# Connectors.net
KiCad netlist of a schematic drawn in Altium Designer
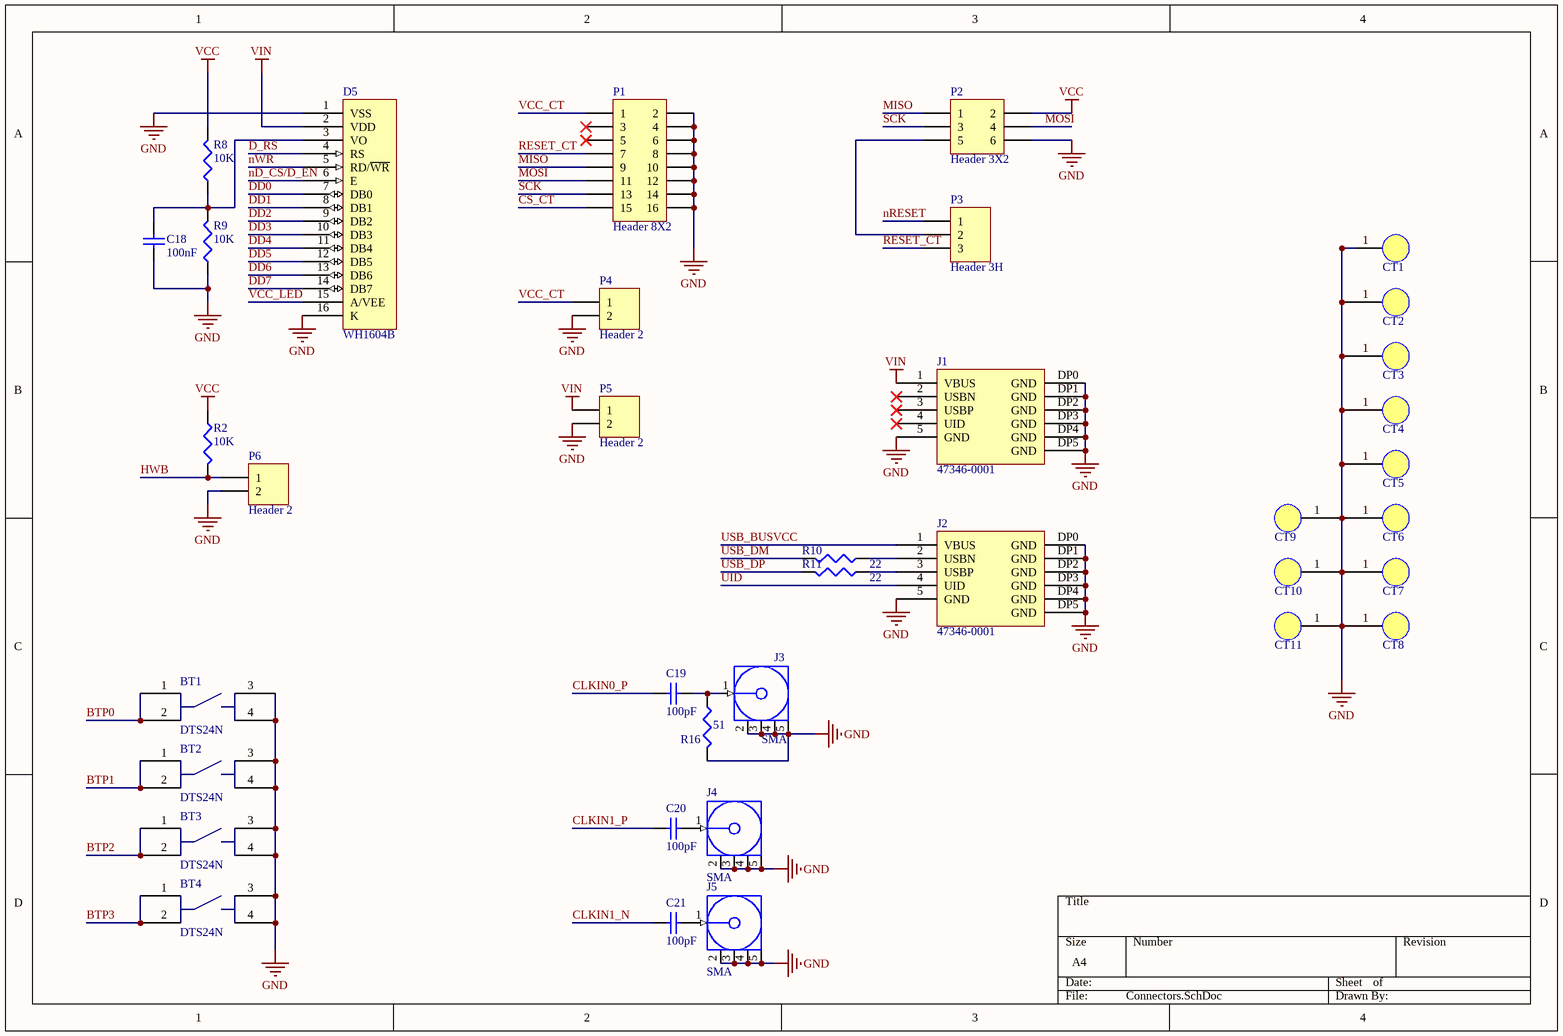
[diagram p0: Connectors.SchDoc]

(export (version "E")
  (design (tool "Eeschema 10.0.6"))
  (components
    (comp (ref "BT1") (value "DTS24N") (footprint "DTS24N") (libsource (lib "CTMBLib") (part "DTS24N")))
    (comp (ref "BT2") (value "DTS24N") (footprint "DTS24N") (libsource (lib "CTMBLib") (part "DTS24N")))
    (comp (ref "BT3") (value "DTS24N") (footprint "DTS24N") (libsource (lib "CTMBLib") (part "DTS24N")))
    (comp (ref "BT4") (value "DTS24N") (footprint "DTS24N") (libsource (lib "CTMBLib") (part "DTS24N")))
    (comp (ref "C18")
      (value "100nF")
      (footprint "1608[0603]")
      (description "Capacitor (Semiconductor SIM Model)")
      (fields (field (name "PUBLISHER") "Altium Limited"))
      (libsource (lib "Miscellaneous Devices") (part "Cap Semi"))
    )
    (comp (ref "C19")
      (value "100pF")
      (footprint "1608[0603]")
      (description "Capacitor (Semiconductor SIM Model)")
      (fields (field (name "PUBLISHER") "Altium Limited"))
      (libsource (lib "Miscellaneous Devices") (part "Cap Semi"))
    )
    (comp (ref "C20")
      (value "100pF")
      (footprint "1608[0603]")
      (description "Capacitor (Semiconductor SIM Model)")
      (fields (field (name "PUBLISHER") "Altium Limited"))
      (libsource (lib "Miscellaneous Devices") (part "Cap Semi"))
    )
    (comp (ref "C21")
      (value "100pF")
      (footprint "1608[0603]")
      (description "Capacitor (Semiconductor SIM Model)")
      (fields (field (name "PUBLISHER") "Altium Limited"))
      (libsource (lib "Miscellaneous Devices") (part "Cap Semi"))
    )
    (comp (ref "CT1")
      (value "MTHOLE_3mm")
      (footprint "MTHOLE")
      (libsource (lib "CTMBLib") (part "MTHOLE_3mm"))
    )
    (comp (ref "CT2")
      (value "MTHOLE_3mm")
      (footprint "MTHOLE")
      (libsource (lib "CTMBLib") (part "MTHOLE_3mm"))
    )
    (comp (ref "CT3")
      (value "MTHOLE_3mm")
      (footprint "MTHOLE")
      (libsource (lib "CTMBLib") (part "MTHOLE_3mm"))
    )
    (comp (ref "CT4")
      (value "MTHOLE_3mm")
      (footprint "MTHOLE")
      (libsource (lib "CTMBLib") (part "MTHOLE_3mm"))
    )
    (comp (ref "CT5")
      (value "MTHOLE_3mm")
      (footprint "MTHOLE")
      (libsource (lib "CTMBLib") (part "MTHOLE_3mm"))
    )
    (comp (ref "CT6")
      (value "MTHOLE_3mm")
      (footprint "MTHOLE")
      (libsource (lib "CTMBLib") (part "MTHOLE_3mm"))
    )
    (comp (ref "CT7")
      (value "MTHOLE_3mm")
      (footprint "MTHOLE")
      (libsource (lib "CTMBLib") (part "MTHOLE_3mm"))
    )
    (comp (ref "CT8")
      (value "MTHOLE_3mm")
      (footprint "MTHOLE")
      (libsource (lib "CTMBLib") (part "MTHOLE_3mm"))
    )
    (comp (ref "CT9")
      (value "MTHOLE_3mm")
      (footprint "MTHOLE")
      (libsource (lib "CTMBLib") (part "MTHOLE_3mm"))
    )
    (comp (ref "CT10")
      (value "MTHOLE_3mm")
      (footprint "MTHOLE")
      (libsource (lib "CTMBLib") (part "MTHOLE_3mm"))
    )
    (comp (ref "CT11")
      (value "MTHOLE_3mm")
      (footprint "MTHOLE")
      (libsource (lib "CTMBLib") (part "MTHOLE_3mm"))
    )
    (comp (ref "D5") (value "WH1604B") (footprint "WH1604A") (libsource (lib "CTMBLib") (part "WH1604B")))
    (comp (ref "J1")
      (value "47346-0001")
      (footprint "USB_MICRO")
      (description "Micro USB Molex")
      (libsource (lib "CTMBLib") (part "47346-0001"))
    )
    (comp (ref "J2")
      (value "47346-0001")
      (footprint "USB_MICRO")
      (description "Micro USB Molex")
      (libsource (lib "CTMBLib") (part "47346-0001"))
    )
    (comp (ref "J3") (value "SMA") (footprint "SMA") (libsource (lib "Integrated_Library1") (part "SMA")))
    (comp (ref "J4") (value "SMA") (footprint "SMA") (libsource (lib "Integrated_Library1") (part "SMA")))
    (comp (ref "J5") (value "SMA") (footprint "SMA") (libsource (lib "Integrated_Library1") (part "SMA")))
    (comp (ref "P1")
      (value "Header 8X2")
      (footprint "HDR2X8")
      (description "Header, 8-Pin, Dual row")
      (fields (field (name "PUBLISHER") "Altium Limited"))
      (libsource (lib "Miscellaneous Connectors") (part "Header 8X2"))
    )
    (comp (ref "P2")
      (value "Header 3X2")
      (footprint "HDR2X3")
      (description "Header, 3-Pin, Dual row")
      (fields (field (name "PUBLISHER") "Altium Limited"))
      (libsource (lib "Miscellaneous Connectors") (part "Header 3X2"))
    )
    (comp (ref "P3")
      (value "Header 3H")
      (footprint "HDR1X3H")
      (description "Header, 3-Pin, Right Angle")
      (fields (field (name "PUBLISHER") "Altium Limited"))
      (libsource (lib "Miscellaneous Connectors") (part "Header 3H"))
    )
    (comp (ref "P4")
      (value "Header 2")
      (footprint "HDR1X2")
      (description "Header, 2-Pin")
      (fields (field (name "PUBLISHER") "Altium Limited"))
      (libsource (lib "Miscellaneous Connectors") (part "Header 2"))
    )
    (comp (ref "P5")
      (value "Header 2")
      (footprint "HDR1X2")
      (description "Header, 2-Pin")
      (fields (field (name "PUBLISHER") "Altium Limited"))
      (libsource (lib "Miscellaneous Connectors") (part "Header 2"))
    )
    (comp (ref "P6")
      (value "Header 2")
      (footprint "HDR1X2")
      (description "Header, 2-Pin")
      (fields (field (name "PUBLISHER") "Altium Limited"))
      (libsource (lib "Miscellaneous Connectors") (part "Header 2"))
    )
    (comp (ref "R2")
      (value "10K")
      (footprint "J1-0603")
      (description "Resistor")
      (fields (field (name "PUBLISHER") "Altium Limited"))
      (libsource (lib "Miscellaneous Devices") (part "Res3"))
    )
    (comp (ref "R8")
      (value "10K")
      (footprint "J1-0603")
      (description "Resistor")
      (fields (field (name "PUBLISHER") "Altium Limited"))
      (libsource (lib "Miscellaneous Devices") (part "Res3"))
    )
    (comp (ref "R9")
      (value "10K")
      (footprint "J1-0603")
      (description "Resistor")
      (fields (field (name "PUBLISHER") "Altium Limited"))
      (libsource (lib "Miscellaneous Devices") (part "Res3"))
    )
    (comp (ref "R10")
      (value "22")
      (footprint "J1-0603")
      (description "Resistor")
      (fields (field (name "PUBLISHER") "Altium Limited"))
      (libsource (lib "Miscellaneous Devices") (part "Res3"))
    )
    (comp (ref "R11")
      (value "22")
      (footprint "J1-0603")
      (description "Resistor")
      (fields (field (name "PUBLISHER") "Altium Limited"))
      (libsource (lib "Miscellaneous Devices") (part "Res3"))
    )
    (comp (ref "R16")
      (value "51")
      (footprint "J1-0603")
      (description "Resistor")
      (fields (field (name "PUBLISHER") "Altium Limited"))
      (libsource (lib "Miscellaneous Devices") (part "Res3"))
    )
  )
  (nets
    (net (code "1") (name "/BTP0") (class "Default")
      (node (ref "BT1") (pin "1") (pinfunction "1_1") (pintype "passive"))
      (node (ref "BT1") (pin "2") (pinfunction "2_2") (pintype "passive"))
    )
    (net (code "2") (name "/BTP1") (class "Default")
      (node (ref "BT2") (pin "1") (pinfunction "1_1") (pintype "passive"))
      (node (ref "BT2") (pin "2") (pinfunction "2_2") (pintype "passive"))
    )
    (net (code "3") (name "/BTP2") (class "Default")
      (node (ref "BT3") (pin "1") (pinfunction "1_1") (pintype "passive"))
      (node (ref "BT3") (pin "2") (pinfunction "2_2") (pintype "passive"))
    )
    (net (code "4") (name "/BTP3") (class "Default")
      (node (ref "BT4") (pin "1") (pinfunction "1_1") (pintype "passive"))
      (node (ref "BT4") (pin "2") (pinfunction "2_2") (pintype "passive"))
    )
    (net (code "5") (name "/CLKIN0_P") (class "Default")
      (node (ref "C19") (pin "2") (pinfunction "2_2") (pintype "passive"))
    )
    (net (code "6") (name "/CLKIN1_N") (class "Default")
      (node (ref "C21") (pin "2") (pinfunction "2_2") (pintype "passive"))
    )
    (net (code "7") (name "/CLKIN1_P") (class "Default")
      (node (ref "C20") (pin "2") (pinfunction "2_2") (pintype "passive"))
    )
    (net (code "8") (name "/CS_CT") (class "Default")
      (node (ref "P1") (pin "15") (pinfunction "15_15") (pintype "passive"))
    )
    (net (code "9") (name "/DD0") (class "Default")
      (node (ref "D5") (pin "7") (pinfunction "DB0_7") (pintype "bidirectional"))
    )
    (net (code "10") (name "/DD1") (class "Default")
      (node (ref "D5") (pin "8") (pinfunction "DB1_8") (pintype "bidirectional"))
    )
    (net (code "11") (name "/DD2") (class "Default")
      (node (ref "D5") (pin "9") (pinfunction "DB2_9") (pintype "bidirectional"))
    )
    (net (code "12") (name "/DD3") (class "Default")
      (node (ref "D5") (pin "10") (pinfunction "DB3_10") (pintype "bidirectional"))
    )
    (net (code "13") (name "/DD4") (class "Default")
      (node (ref "D5") (pin "11") (pinfunction "DB4_11") (pintype "bidirectional"))
    )
    (net (code "14") (name "/DD5") (class "Default")
      (node (ref "D5") (pin "12") (pinfunction "DB5_12") (pintype "bidirectional"))
    )
    (net (code "15") (name "/DD6") (class "Default")
      (node (ref "D5") (pin "13") (pinfunction "DB6_13") (pintype "bidirectional"))
    )
    (net (code "16") (name "/DD7") (class "Default")
      (node (ref "D5") (pin "14") (pinfunction "DB7_14") (pintype "bidirectional"))
    )
    (net (code "17") (name "/D_RS") (class "Default")
      (node (ref "D5") (pin "4") (pinfunction "RS_4") (pintype "input"))
    )
    (net (code "18") (name "/HWB") (class "Default")
      (node (ref "P6") (pin "1") (pinfunction "1_1") (pintype "passive"))
      (node (ref "R2") (pin "2") (pinfunction "2_2") (pintype "passive"))
    )
    (net (code "19") (name "/MISO") (class "Default")
      (node (ref "P1") (pin "9") (pinfunction "9_9") (pintype "passive"))
      (node (ref "P2") (pin "1") (pinfunction "1_1") (pintype "passive"))
    )
    (net (code "20") (name "/MOSI") (class "Default")
      (node (ref "P1") (pin "11") (pinfunction "11_11") (pintype "passive"))
      (node (ref "P2") (pin "4") (pinfunction "4_4") (pintype "passive"))
    )
    (net (code "21") (name "/RESET_CT") (class "Default")
      (node (ref "P1") (pin "7") (pinfunction "7_7") (pintype "passive"))
      (node (ref "P3") (pin "3") (pinfunction "3_3") (pintype "passive"))
    )
    (net (code "22") (name "/SCK") (class "Default")
      (node (ref "P1") (pin "13") (pinfunction "13_13") (pintype "passive"))
      (node (ref "P2") (pin "3") (pinfunction "3_3") (pintype "passive"))
    )
    (net (code "23") (name "/UID") (class "Default")
      (node (ref "J2") (pin "4") (pinfunction "UID_4") (pintype "passive"))
    )
    (net (code "24") (name "/USB_BUSVCC") (class "Default")
      (node (ref "J2") (pin "1") (pinfunction "VBUS_1") (pintype "passive"))
    )
    (net (code "25") (name "/USB_DM") (class "Default")
      (node (ref "R10") (pin "2") (pinfunction "2_2") (pintype "passive"))
    )
    (net (code "26") (name "/USB_DP") (class "Default")
      (node (ref "R11") (pin "2") (pinfunction "2_2") (pintype "passive"))
    )
    (net (code "27") (name "/VCC_CT") (class "Default")
      (node (ref "P1") (pin "1") (pinfunction "1_1") (pintype "passive"))
      (node (ref "P4") (pin "1") (pinfunction "1_1") (pintype "passive"))
    )
    (net (code "28") (name "/VCC_LED") (class "Default")
      (node (ref "D5") (pin "15") (pinfunction "A/VEE_15") (pintype "power_in"))
    )
    (net (code "29") (name "/nD_CS{slash}D_EN") (class "Default")
      (node (ref "D5") (pin "6") (pinfunction "E_6") (pintype "input"))
    )
    (net (code "30") (name "/nRESET") (class "Default")
      (node (ref "P3") (pin "1") (pinfunction "1_1") (pintype "passive"))
    )
    (net (code "31") (name "/nWR") (class "Default")
      (node (ref "D5") (pin "5") (pinfunction "RD/~{WR}_5") (pintype "input"))
    )
    (net (code "32") (name "GND") (class "Default")
      (node (ref "BT1") (pin "3") (pinfunction "3_3") (pintype "passive"))
      (node (ref "BT1") (pin "4") (pinfunction "4_4") (pintype "passive"))
      (node (ref "BT2") (pin "3") (pinfunction "3_3") (pintype "passive"))
      (node (ref "BT2") (pin "4") (pinfunction "4_4") (pintype "passive"))
      (node (ref "BT3") (pin "3") (pinfunction "3_3") (pintype "passive"))
      (node (ref "BT3") (pin "4") (pinfunction "4_4") (pintype "passive"))
      (node (ref "BT4") (pin "3") (pinfunction "3_3") (pintype "passive"))
      (node (ref "BT4") (pin "4") (pinfunction "4_4") (pintype "passive"))
      (node (ref "C18") (pin "2") (pinfunction "2_2") (pintype "passive"))
      (node (ref "CT1") (pin "1") (pinfunction "1_1") (pintype "passive"))
      (node (ref "CT10") (pin "1") (pinfunction "1_1") (pintype "passive"))
      (node (ref "CT11") (pin "1") (pinfunction "1_1") (pintype "passive"))
      (node (ref "CT2") (pin "1") (pinfunction "1_1") (pintype "passive"))
      (node (ref "CT3") (pin "1") (pinfunction "1_1") (pintype "passive"))
      (node (ref "CT4") (pin "1") (pinfunction "1_1") (pintype "passive"))
      (node (ref "CT5") (pin "1") (pinfunction "1_1") (pintype "passive"))
      (node (ref "CT6") (pin "1") (pinfunction "1_1") (pintype "passive"))
      (node (ref "CT7") (pin "1") (pinfunction "1_1") (pintype "passive"))
      (node (ref "CT8") (pin "1") (pinfunction "1_1") (pintype "passive"))
      (node (ref "CT9") (pin "1") (pinfunction "1_1") (pintype "passive"))
      (node (ref "D5") (pin "1") (pinfunction "VSS_1") (pintype "power_in"))
      (node (ref "D5") (pin "16") (pinfunction "K_16") (pintype "power_in"))
      (node (ref "J1") (pin "5") (pinfunction "GND_5") (pintype "passive"))
      (node (ref "J1") (pin "DP0") (pinfunction "GND_DP0") (pintype "passive"))
      (node (ref "J1") (pin "DP1") (pinfunction "GND_DP1") (pintype "passive"))
      (node (ref "J1") (pin "DP2") (pinfunction "GND_DP2") (pintype "passive"))
      (node (ref "J1") (pin "DP3") (pinfunction "GND_DP3") (pintype "passive"))
      (node (ref "J1") (pin "DP4") (pinfunction "GND_DP4") (pintype "passive"))
      (node (ref "J1") (pin "DP5") (pinfunction "GND_DP5") (pintype "passive"))
      (node (ref "J2") (pin "5") (pinfunction "GND_5") (pintype "passive"))
      (node (ref "J2") (pin "DP0") (pinfunction "GND_DP0") (pintype "passive"))
      (node (ref "J2") (pin "DP1") (pinfunction "GND_DP1") (pintype "passive"))
      (node (ref "J2") (pin "DP2") (pinfunction "GND_DP2") (pintype "passive"))
      (node (ref "J2") (pin "DP3") (pinfunction "GND_DP3") (pintype "passive"))
      (node (ref "J2") (pin "DP4") (pinfunction "GND_DP4") (pintype "passive"))
      (node (ref "J2") (pin "DP5") (pinfunction "GND_DP5") (pintype "passive"))
      (node (ref "J3") (pin "2") (pinfunction "GND_2") (pintype "power_in"))
      (node (ref "J3") (pin "3") (pinfunction "GND_3") (pintype "power_in"))
      (node (ref "J3") (pin "4") (pinfunction "GND_4") (pintype "power_in"))
      (node (ref "J3") (pin "5") (pinfunction "GND_5") (pintype "power_in"))
      (node (ref "J4") (pin "2") (pinfunction "GND_2") (pintype "power_in"))
      (node (ref "J4") (pin "3") (pinfunction "GND_3") (pintype "power_in"))
      (node (ref "J4") (pin "4") (pinfunction "GND_4") (pintype "power_in"))
      (node (ref "J4") (pin "5") (pinfunction "GND_5") (pintype "power_in"))
      (node (ref "J5") (pin "2") (pinfunction "GND_2") (pintype "power_in"))
      (node (ref "J5") (pin "3") (pinfunction "GND_3") (pintype "power_in"))
      (node (ref "J5") (pin "4") (pinfunction "GND_4") (pintype "power_in"))
      (node (ref "J5") (pin "5") (pinfunction "GND_5") (pintype "power_in"))
      (node (ref "P1") (pin "10") (pinfunction "10_10") (pintype "passive"))
      (node (ref "P1") (pin "12") (pinfunction "12_12") (pintype "passive"))
      (node (ref "P1") (pin "14") (pinfunction "14_14") (pintype "passive"))
      (node (ref "P1") (pin "16") (pinfunction "16_16") (pintype "passive"))
      (node (ref "P1") (pin "2") (pinfunction "2_2") (pintype "passive"))
      (node (ref "P1") (pin "4") (pinfunction "4_4") (pintype "passive"))
      (node (ref "P1") (pin "6") (pinfunction "6_6") (pintype "passive"))
      (node (ref "P1") (pin "8") (pinfunction "8_8") (pintype "passive"))
      (node (ref "P2") (pin "6") (pinfunction "6_6") (pintype "passive"))
      (node (ref "P4") (pin "2") (pinfunction "2_2") (pintype "passive"))
      (node (ref "P5") (pin "2") (pinfunction "2_2") (pintype "passive"))
      (node (ref "P6") (pin "2") (pinfunction "2_2") (pintype "passive"))
      (node (ref "R16") (pin "2") (pinfunction "2_2") (pintype "passive"))
      (node (ref "R9") (pin "1") (pinfunction "1_1") (pintype "passive"))
    )
    (net (code "33") (name "Net-(D5-VO)") (class "Default")
      (node (ref "C18") (pin "1") (pinfunction "1_1") (pintype "passive"))
      (node (ref "D5") (pin "3") (pinfunction "VO_3") (pintype "power_in"))
      (node (ref "R8") (pin "1") (pinfunction "1_1") (pintype "passive"))
      (node (ref "R9") (pin "2") (pinfunction "2_2") (pintype "passive"))
    )
    (net (code "34") (name "Net-(J2-USBN)") (class "Default")
      (node (ref "J2") (pin "2") (pinfunction "USBN_2") (pintype "passive"))
      (node (ref "R10") (pin "1") (pinfunction "1_1") (pintype "passive"))
    )
    (net (code "35") (name "Net-(J2-USBP)") (class "Default")
      (node (ref "J2") (pin "3") (pinfunction "USBP_3") (pintype "passive"))
      (node (ref "R11") (pin "1") (pinfunction "1_1") (pintype "passive"))
    )
    (net (code "36") (name "Net-(J3-Signal)") (class "Default")
      (node (ref "C19") (pin "1") (pinfunction "1_1") (pintype "passive"))
      (node (ref "J3") (pin "1") (pinfunction "Signal_1") (pintype "input"))
      (node (ref "R16") (pin "1") (pinfunction "1_1") (pintype "passive"))
    )
    (net (code "37") (name "Net-(J4-Signal)") (class "Default")
      (node (ref "C20") (pin "1") (pinfunction "1_1") (pintype "passive"))
      (node (ref "J4") (pin "1") (pinfunction "Signal_1") (pintype "input"))
    )
    (net (code "38") (name "Net-(J5-Signal)") (class "Default")
      (node (ref "C21") (pin "1") (pinfunction "1_1") (pintype "passive"))
      (node (ref "J5") (pin "1") (pinfunction "Signal_1") (pintype "input"))
    )
    (net (code "39") (name "Net-(P2-Pad5)") (class "Default")
      (node (ref "P2") (pin "5") (pinfunction "5_5") (pintype "passive"))
      (node (ref "P3") (pin "2") (pinfunction "2_2") (pintype "passive"))
    )
    (net (code "40") (name "VCC") (class "Default")
      (node (ref "P2") (pin "2") (pinfunction "2_2") (pintype "passive"))
      (node (ref "R2") (pin "1") (pinfunction "1_1") (pintype "passive"))
      (node (ref "R8") (pin "2") (pinfunction "2_2") (pintype "passive"))
    )
    (net (code "41") (name "VIN") (class "Default")
      (node (ref "D5") (pin "2") (pinfunction "VDD_2") (pintype "power_in"))
      (node (ref "J1") (pin "1") (pinfunction "VBUS_1") (pintype "passive"))
      (node (ref "P5") (pin "1") (pinfunction "1_1") (pintype "passive"))
    )
    (net (code "42") (name "unconnected-(J1-UID-Pad4)") (class "Default")
      (node (ref "J1") (pin "4") (pinfunction "UID_4") (pintype "passive+no_connect"))
    )
    (net (code "43") (name "unconnected-(J1-USBN-Pad2)") (class "Default")
      (node (ref "J1") (pin "2") (pinfunction "USBN_2") (pintype "passive+no_connect"))
    )
    (net (code "44") (name "unconnected-(J1-USBP-Pad3)") (class "Default")
      (node (ref "J1") (pin "3") (pinfunction "USBP_3") (pintype "passive+no_connect"))
    )
    (net (code "45") (name "unconnected-(P1-Pad3)") (class "Default")
      (node (ref "P1") (pin "3") (pinfunction "3_3") (pintype "passive+no_connect"))
    )
    (net (code "46") (name "unconnected-(P1-Pad5)") (class "Default")
      (node (ref "P1") (pin "5") (pinfunction "5_5") (pintype "passive+no_connect"))
    )
  )
)
